# CAN_toolboard_redesign.net
KiCad netlist of a schematic drawn in EAGLE
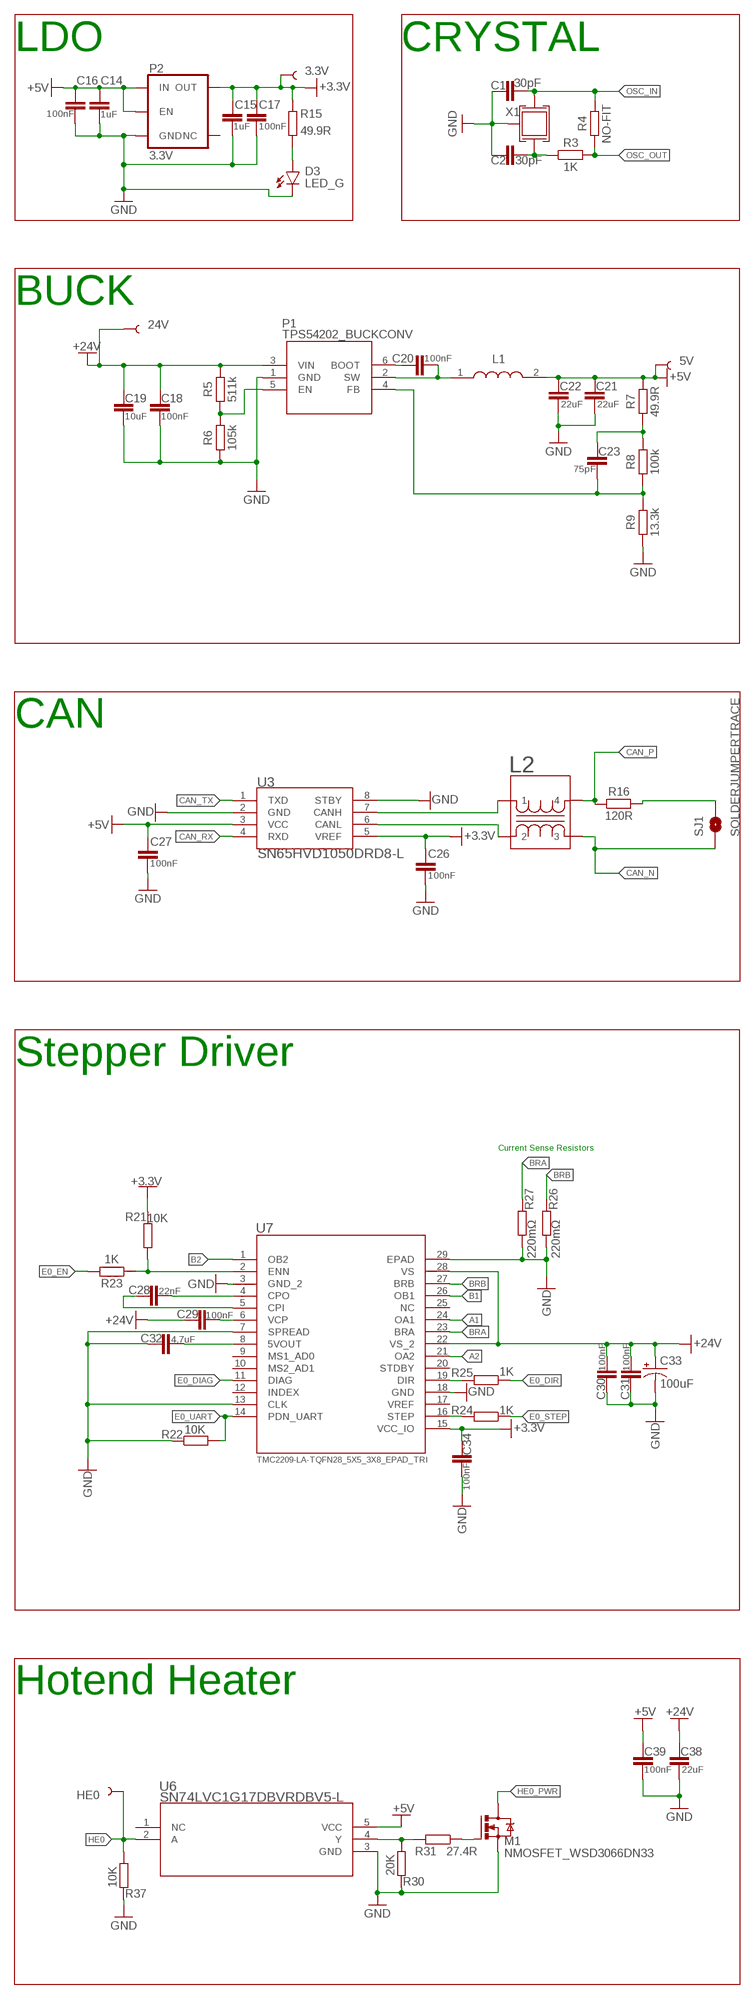
[diagram p0: schematic, sheet 1, part 1 of 2]
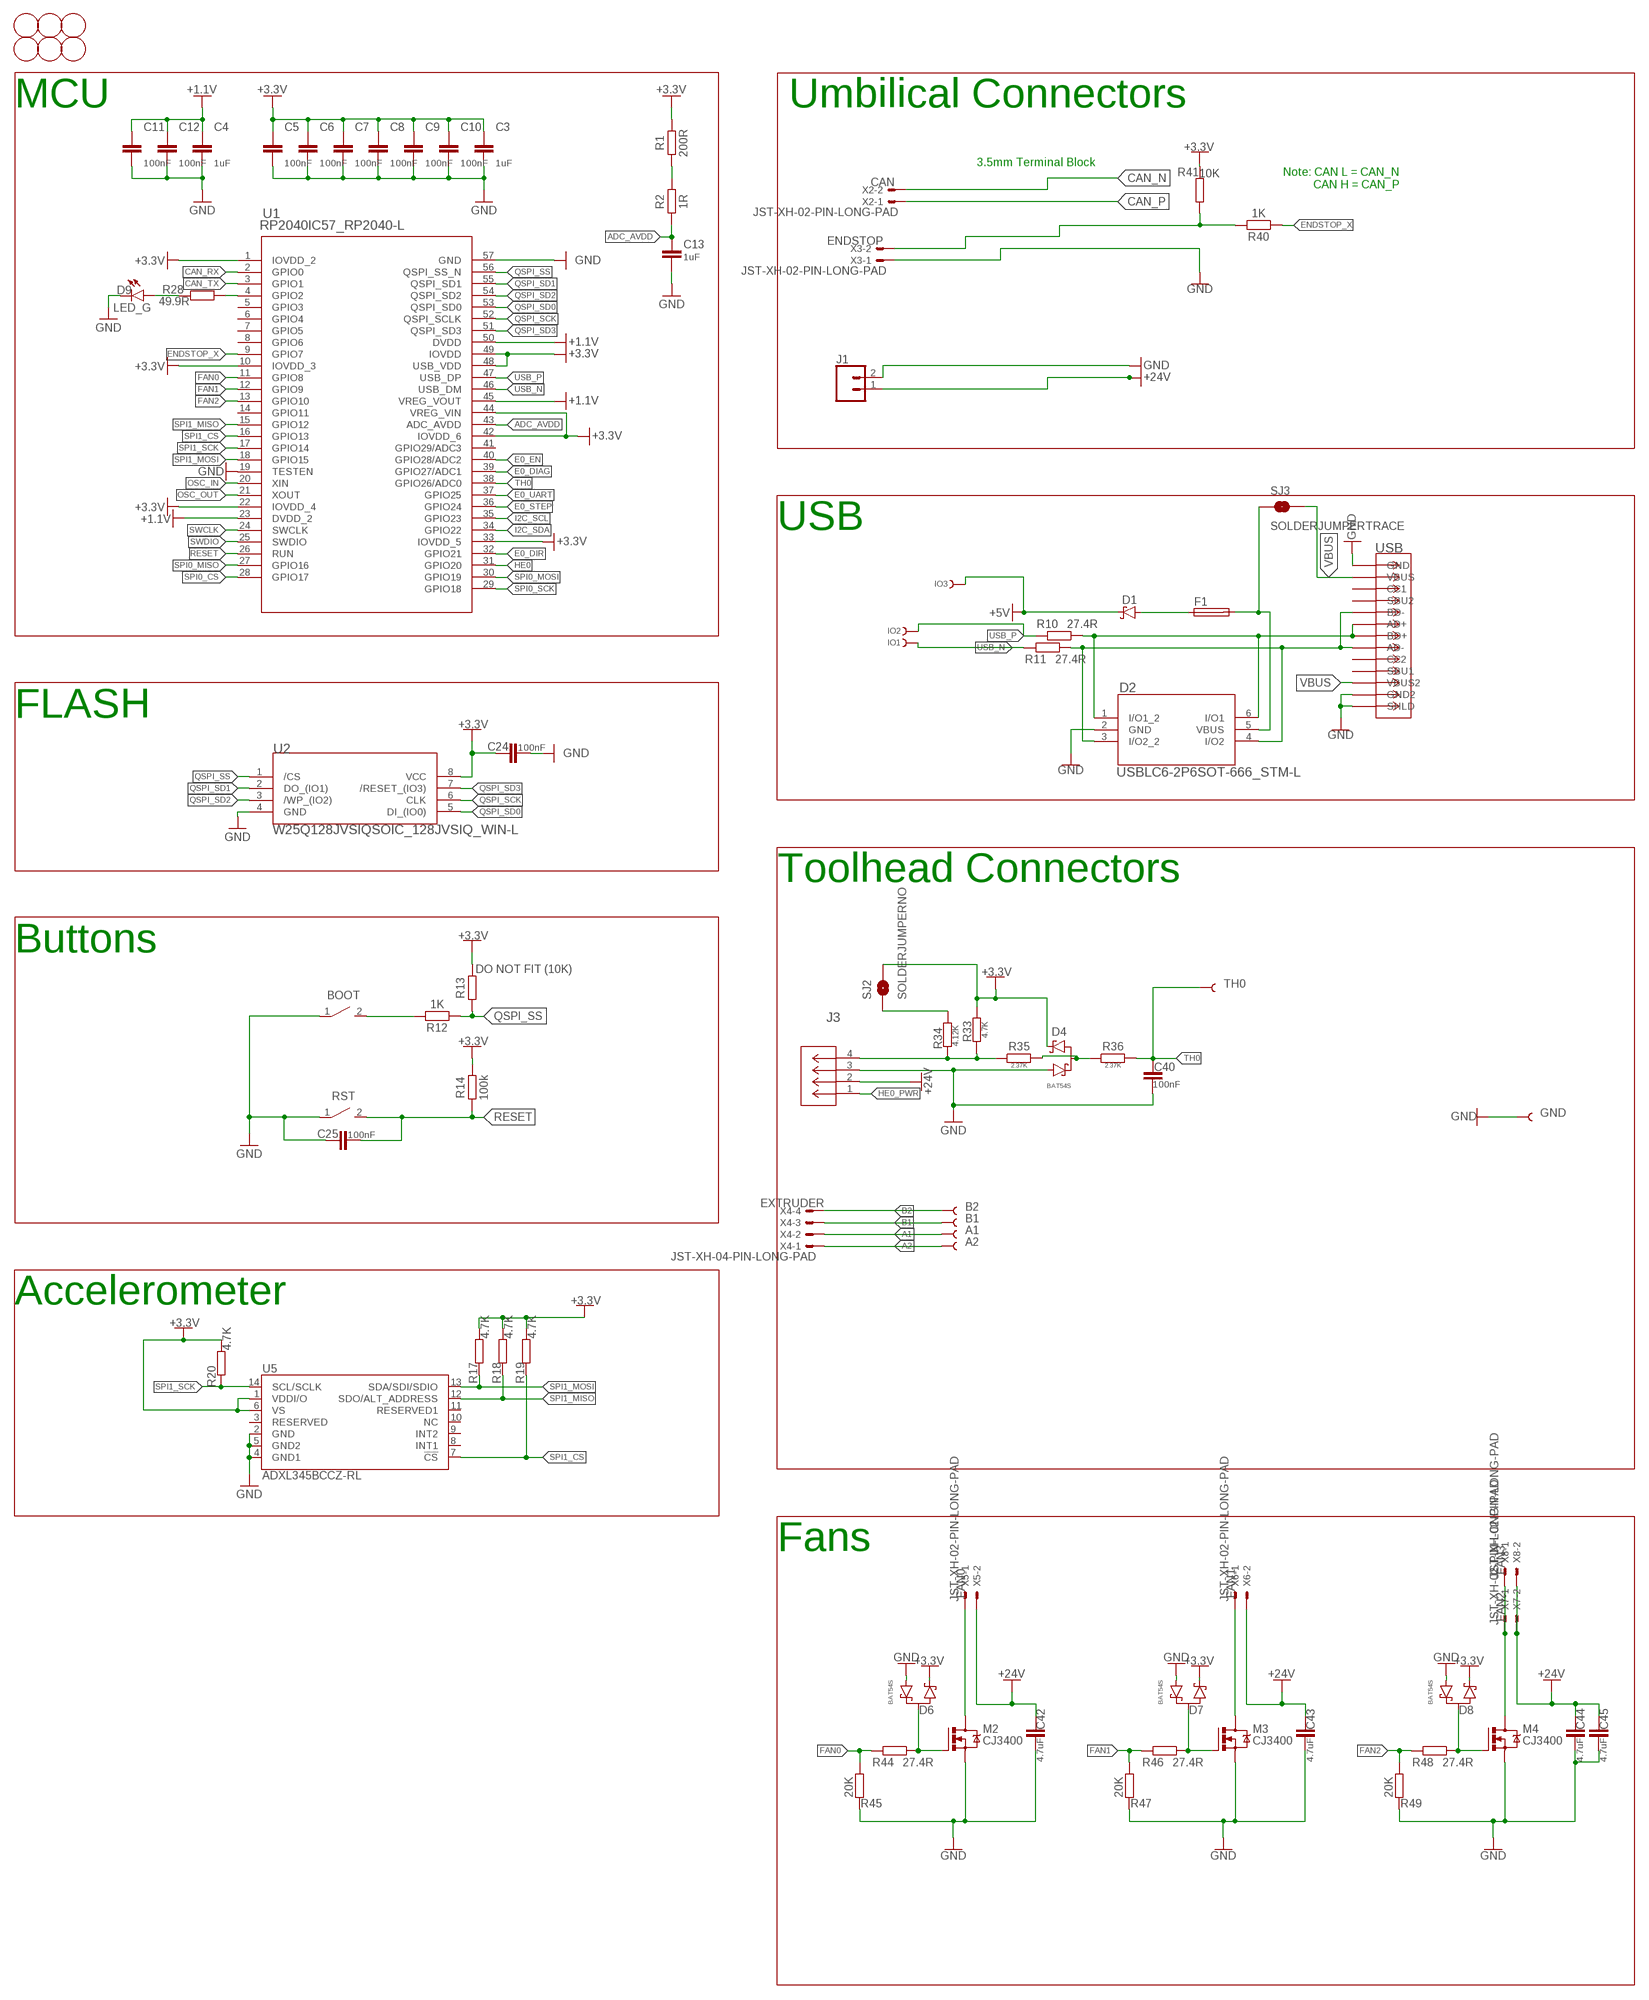
[diagram p1: schematic, sheet 1, part 2 of 2]

(export (version "E")
  (design (tool "Eeschema 10.0.6"))
  (components
    (comp (ref "3.3V")
      (value "TEST-POINT3X4")
      (footprint "eagle-import:PAD.03X.04")
      (libsource (lib "eagle-import") (part "TEST-POINT3X4"))
    )
    (comp (ref "5V")
      (value "TEST-POINT3X4")
      (footprint "eagle-import:PAD.03X.04")
      (libsource (lib "eagle-import") (part "TEST-POINT3X4"))
    )
    (comp (ref "24V")
      (value "TEST-POINT3X4")
      (footprint "eagle-import:PAD.03X.04")
      (libsource (lib "eagle-import") (part "TEST-POINT3X4"))
    )
    (comp (ref "A1")
      (value "TEST-POINT3X4")
      (footprint "eagle-import:PAD.03X.04")
      (libsource (lib "eagle-import") (part "TEST-POINT3X4"))
    )
    (comp (ref "A2")
      (value "TEST-POINT3X4")
      (footprint "eagle-import:PAD.03X.04")
      (libsource (lib "eagle-import") (part "TEST-POINT3X4"))
    )
    (comp (ref "B1")
      (value "TEST-POINT3X4")
      (footprint "eagle-import:PAD.03X.04")
      (libsource (lib "eagle-import") (part "TEST-POINT3X4"))
    )
    (comp (ref "B2")
      (value "TEST-POINT3X4")
      (footprint "eagle-import:PAD.03X.04")
      (libsource (lib "eagle-import") (part "TEST-POINT3X4"))
    )
    (comp (ref "BOOT")
      (value "B3U-1000P(M)-B")
      (footprint "eagle-import:B3U-1000P(M)-B")
      (fields (field (name "MANUFACTURER") "OMRON"))
      (libsource (lib "eagle-import") (part "B3U-X0001000P(M)-BB3U-1000P(M)-B"))
    )
    (comp (ref "C1")
      (value "30pF")
      (footprint "eagle-import:CAPC1005X60")
      (libsource (lib "eagle-import") (part "CCHIP-0402(1005-METRIC)_"))
    )
    (comp (ref "C2")
      (value "30pF")
      (footprint "eagle-import:CAPC1005X60")
      (libsource (lib "eagle-import") (part "CCHIP-0402(1005-METRIC)_"))
    )
    (comp (ref "C3")
      (value "1uF")
      (footprint "eagle-import:CAPC1005X60")
      (libsource (lib "eagle-import") (part "CCHIP-0402(1005-METRIC)_"))
    )
    (comp (ref "C4")
      (value "1uF")
      (footprint "eagle-import:CAPC1005X60")
      (libsource (lib "eagle-import") (part "CCHIP-0402(1005-METRIC)_"))
    )
    (comp (ref "C5")
      (value "100nF")
      (footprint "eagle-import:CAPC1005X60")
      (libsource (lib "eagle-import") (part "CCHIP-0402(1005-METRIC)_"))
    )
    (comp (ref "C6")
      (value "100nF")
      (footprint "eagle-import:CAPC1005X60")
      (libsource (lib "eagle-import") (part "CCHIP-0402(1005-METRIC)_"))
    )
    (comp (ref "C7")
      (value "100nF")
      (footprint "eagle-import:CAPC1005X60")
      (libsource (lib "eagle-import") (part "CCHIP-0402(1005-METRIC)_"))
    )
    (comp (ref "C8")
      (value "100nF")
      (footprint "eagle-import:CAPC1005X60")
      (libsource (lib "eagle-import") (part "CCHIP-0402(1005-METRIC)_"))
    )
    (comp (ref "C9")
      (value "100nF")
      (footprint "eagle-import:CAPC1005X60")
      (libsource (lib "eagle-import") (part "CCHIP-0402(1005-METRIC)_"))
    )
    (comp (ref "C10")
      (value "100nF")
      (footprint "eagle-import:CAPC1005X60")
      (libsource (lib "eagle-import") (part "CCHIP-0402(1005-METRIC)_"))
    )
    (comp (ref "C11")
      (value "100nF")
      (footprint "eagle-import:CAPC1005X60")
      (libsource (lib "eagle-import") (part "CCHIP-0402(1005-METRIC)_"))
    )
    (comp (ref "C12")
      (value "100nF")
      (footprint "eagle-import:CAPC1005X60")
      (libsource (lib "eagle-import") (part "CCHIP-0402(1005-METRIC)_"))
    )
    (comp (ref "C13")
      (value "1uF")
      (footprint "eagle-import:CAPC1005X60")
      (libsource (lib "eagle-import") (part "CCHIP-0402(1005-METRIC)_"))
    )
    (comp (ref "C14")
      (value "1uF")
      (footprint "eagle-import:CAPC1005X60")
      (libsource (lib "eagle-import") (part "CCHIP-0402(1005-METRIC)_"))
    )
    (comp (ref "C15")
      (value "1uF")
      (footprint "eagle-import:CAPC1005X60")
      (libsource (lib "eagle-import") (part "CCHIP-0402(1005-METRIC)_"))
    )
    (comp (ref "C16")
      (value "100nF")
      (footprint "eagle-import:CAPC1005X60")
      (libsource (lib "eagle-import") (part "CCHIP-0402(1005-METRIC)_"))
    )
    (comp (ref "C17")
      (value "100nF")
      (footprint "eagle-import:CAPC1005X60")
      (libsource (lib "eagle-import") (part "CCHIP-0402(1005-METRIC)_"))
    )
    (comp (ref "C18")
      (value "100nF")
      (footprint "eagle-import:CAPC1005X60")
      (libsource (lib "eagle-import") (part "CCHIP-0402(1005-METRIC)_"))
    )
    (comp (ref "C19")
      (value "10uF")
      (footprint "eagle-import:CAPC1608X85")
      (libsource (lib "eagle-import") (part "CCHIP-0603(1608-METRIC)_"))
    )
    (comp (ref "C20")
      (value "100nF")
      (footprint "eagle-import:CAPC1005X60")
      (libsource (lib "eagle-import") (part "CCHIP-0402(1005-METRIC)_"))
    )
    (comp (ref "C21")
      (value "22uF")
      (footprint "eagle-import:CAPC2012X110")
      (libsource (lib "eagle-import") (part "CCHIP-0805(2012-METRIC)_"))
    )
    (comp (ref "C22")
      (value "22uF")
      (footprint "eagle-import:CAPC2012X110")
      (libsource (lib "eagle-import") (part "CCHIP-0805(2012-METRIC)_"))
    )
    (comp (ref "C23")
      (value "75pF")
      (footprint "eagle-import:CAPC1005X60")
      (libsource (lib "eagle-import") (part "CCHIP-0402(1005-METRIC)_"))
    )
    (comp (ref "C24")
      (value "100nF")
      (footprint "eagle-import:CAPC1005X60")
      (libsource (lib "eagle-import") (part "CCHIP-0402(1005-METRIC)_"))
    )
    (comp (ref "C25")
      (value "100nF")
      (footprint "eagle-import:CAPC1005X60")
      (libsource (lib "eagle-import") (part "CCHIP-0402(1005-METRIC)_"))
    )
    (comp (ref "C26")
      (value "100nF")
      (footprint "eagle-import:CAPC1005X60")
      (libsource (lib "eagle-import") (part "CCHIP-0402(1005-METRIC)_"))
    )
    (comp (ref "C27")
      (value "100nF")
      (footprint "eagle-import:CAPC1005X60")
      (libsource (lib "eagle-import") (part "CCHIP-0402(1005-METRIC)_"))
    )
    (comp (ref "C28")
      (value "22nF")
      (footprint "eagle-import:CAPC1005X60")
      (libsource (lib "eagle-import") (part "CCHIP-0402(1005-METRIC)_"))
    )
    (comp (ref "C29")
      (value "100nF")
      (footprint "eagle-import:CAPC1005X60")
      (libsource (lib "eagle-import") (part "CCHIP-0402(1005-METRIC)_"))
    )
    (comp (ref "C30")
      (value "100nF")
      (footprint "eagle-import:CAPC1005X60")
      (libsource (lib "eagle-import") (part "CCHIP-0402(1005-METRIC)_"))
    )
    (comp (ref "C31")
      (value "100nF")
      (footprint "eagle-import:CAPC1005X60")
      (libsource (lib "eagle-import") (part "CCHIP-0402(1005-METRIC)_"))
    )
    (comp (ref "C32")
      (value "4.7uF")
      (footprint "eagle-import:CAPC1608X85")
      (libsource (lib "eagle-import") (part "CCHIP-0603(1608-METRIC)_"))
    )
    (comp (ref "C33")
      (value "100uF")
      (footprint "eagle-import:PANASONIC_D")
      (libsource (lib "eagle-import") (part "100UF-POLAR-25V-20%(ELEC)"))
    )
    (comp (ref "C34")
      (value "100nF")
      (footprint "eagle-import:CAPC1005X60")
      (libsource (lib "eagle-import") (part "CCHIP-0402(1005-METRIC)_"))
    )
    (comp (ref "C38")
      (value "22uF")
      (footprint "eagle-import:CAPC2012X110")
      (libsource (lib "eagle-import") (part "CCHIP-0805(2012-METRIC)_"))
    )
    (comp (ref "C39")
      (value "100nF")
      (footprint "eagle-import:CAPC1005X60")
      (libsource (lib "eagle-import") (part "CCHIP-0402(1005-METRIC)_"))
    )
    (comp (ref "C40")
      (value "100nF")
      (footprint "eagle-import:CAPC1005X60")
      (libsource (lib "eagle-import") (part "CCHIP-0402(1005-METRIC)_"))
    )
    (comp (ref "C42")
      (value "4.7uF")
      (footprint "eagle-import:CAPC1608X85")
      (libsource (lib "eagle-import") (part "CCHIP-0603(1608-METRIC)_"))
    )
    (comp (ref "C43")
      (value "4.7uF")
      (footprint "eagle-import:CAPC1608X85")
      (libsource (lib "eagle-import") (part "CCHIP-0603(1608-METRIC)_"))
    )
    (comp (ref "C44")
      (value "4.7uF")
      (footprint "eagle-import:CAPC1608X85")
      (libsource (lib "eagle-import") (part "CCHIP-0603(1608-METRIC)_"))
    )
    (comp (ref "C45")
      (value "4.7uF")
      (footprint "eagle-import:CAPC1608X85")
      (libsource (lib "eagle-import") (part "CCHIP-0603(1608-METRIC)_"))
    )
    (comp (ref "D1")
      (value "MBR0520LT1G")
      (footprint "eagle-import:SODFL3718X115")
      (fields (field (name "MANUFACTURER") "ON Semiconductor"))
      (libsource (lib "eagle-import") (part "SCHOTTKY_DO-219MBR0520LT1G"))
    )
    (comp (ref "D2")
      (value "USBLC6-2P6SOT-666_STM-L")
      (footprint "eagle-import:SOT-666_STM-L")
      (fields
        (field (name "MANUFACTURER_PART_NUMBER") "USBLC6-2P6")
        (field (name "COPYRIGHT") "Copyright (C) 2023 Ultra Librarian. All rights reserved.")
      )
      (libsource (lib "eagle-import") (part "USBLC6-2P6SOT-666_STM-L"))
    )
    (comp (ref "D3")
      (value "LED_G")
      (footprint "eagle-import:LEDC1608X35N_FLAT-G")
      (libsource (lib "eagle-import") (part "CHIP-FLAT-G_0603-0.35MM"))
    )
    (comp (ref "D4")
      (value "BAT54S")
      (footprint "eagle-import:SOT23")
      (libsource (lib "eagle-import") (part "BAT54S"))
    )
    (comp (ref "D6")
      (value "BAT54S")
      (footprint "eagle-import:SOT23")
      (libsource (lib "eagle-import") (part "BAT54S"))
    )
    (comp (ref "D7")
      (value "BAT54S")
      (footprint "eagle-import:SOT23")
      (libsource (lib "eagle-import") (part "BAT54S"))
    )
    (comp (ref "D8")
      (value "BAT54S")
      (footprint "eagle-import:SOT23")
      (libsource (lib "eagle-import") (part "BAT54S"))
    )
    (comp (ref "D9")
      (value "LED_G")
      (footprint "eagle-import:LEDC1608X35N_FLAT-G")
      (libsource (lib "eagle-import") (part "CHIP-FLAT-G_0603-0.35MM"))
    )
    (comp (ref "F1")
      (value "FUSE_CHIP-0603(1608-METRIC)")
      (footprint "eagle-import:FUSC1608X60N")
      (libsource (lib "eagle-import") (part "FUSECHIP-0603(1608-METRIC)_"))
    )
    (comp (ref "FD1")
      (value "FIDUCIAL")
      (footprint "eagle-import:FIDUCIAL_1MM")
      (libsource (lib "eagle-import") (part "FIDUCIAL"))
    )
    (comp (ref "FD2")
      (value "FIDUCIAL")
      (footprint "eagle-import:FIDUCIAL_1MM")
      (libsource (lib "eagle-import") (part "FIDUCIAL"))
    )
    (comp (ref "FD3")
      (value "FIDUCIAL")
      (footprint "eagle-import:FIDUCIAL_1MM")
      (libsource (lib "eagle-import") (part "FIDUCIAL"))
    )
    (comp (ref "FD4")
      (value "FIDUCIAL")
      (footprint "eagle-import:FIDUCIAL_1MM")
      (libsource (lib "eagle-import") (part "FIDUCIAL"))
    )
    (comp (ref "FD5")
      (value "FIDUCIAL")
      (footprint "eagle-import:FIDUCIAL_1MM")
      (libsource (lib "eagle-import") (part "FIDUCIAL"))
    )
    (comp (ref "FD6")
      (value "FIDUCIAL")
      (footprint "eagle-import:FIDUCIAL_1MM")
      (libsource (lib "eagle-import") (part "FIDUCIAL"))
    )
    (comp (ref "GND")
      (value "TEST-POINT3X4")
      (footprint "eagle-import:PAD.03X.04")
      (libsource (lib "eagle-import") (part "TEST-POINT3X4"))
    )
    (comp (ref "HE0")
      (value "TEST-POINT3X4")
      (footprint "eagle-import:PAD.03X.04")
      (libsource (lib "eagle-import") (part "TEST-POINT3X4"))
    )
    (comp (ref "IO1")
      (value "TEST-POINT3")
      (footprint "eagle-import:PAD.03X.03")
      (libsource (lib "eagle-import") (part "TEST-POINT3"))
    )
    (comp (ref "IO2")
      (value "TEST-POINT3")
      (footprint "eagle-import:PAD.03X.03")
      (libsource (lib "eagle-import") (part "TEST-POINT3"))
    )
    (comp (ref "IO3")
      (value "TEST-POINT3")
      (footprint "eagle-import:PAD.03X.03")
      (libsource (lib "eagle-import") (part "TEST-POINT3"))
    )
    (comp (ref "J1")
      (value "CONN_023.5MM")
      (footprint "eagle-import:SCREWTERMINAL-3.5MM-2")
      (libsource (lib "eagle-import") (part "CONN_023.5MM"))
    )
    (comp (ref "J3")
      (value "430450400CON_430450400_MOL")
      (footprint "eagle-import:CON_430450400_MOL")
      (fields
        (field (name "MANUFACTURER_PART_NUMBER") "430450400")
        (field (name "COPYRIGHT") "Copyright (C) 2023 Ultra Librarian. All rights reserved.")
      )
      (libsource (lib "eagle-import") (part "430450400CON_430450400_MOL"))
    )
    (comp (ref "L1")
      (value "ASPI-0630HI-100M-T157X7X4")
      (footprint "eagle-import:SMDRI74-680MT")
      (libsource (lib "eagle-import") (part "ASPI-0630HI-100M-T157X7X4"))
    )
    (comp (ref "L2")
      (value "ACM2012-201-2P-T002ACM2012_TDK")
      (footprint "eagle-import:ACM2012_TDK")
      (fields
        (field (name "MANUFACTURER_PART_NUMBER") "ACM2012-201-2P-T002")
        (field (name "COPYRIGHT") "Copyright (C) 2023 Ultra Librarian. All rights reserved.")
      )
      (libsource (lib "eagle-import") (part "ACM2012-201-2P-T002ACM2012_TDK"))
    )
    (comp (ref "M1")
      (value "NMOSFET_WSD3066DN33")
      (footprint "eagle-import:NMOSFET_WSD3066DN33")
      (libsource (lib "eagle-import") (part "NMOSFET_WSD3066DN33"))
    )
    (comp (ref "M2")
      (value "CJ3400")
      (footprint "eagle-import:SOT23")
      (fields (field (name "MANUFACTURER") "ON Semiconductor") (field (name "MPN") "BSS123L"))
      (libsource (lib "eagle-import") (part "NMOSFET__SOT23-GSDBSS123"))
    )
    (comp (ref "M3")
      (value "CJ3400")
      (footprint "eagle-import:SOT23")
      (fields (field (name "MANUFACTURER") "ON Semiconductor") (field (name "MPN") "BSS123L"))
      (libsource (lib "eagle-import") (part "NMOSFET__SOT23-GSDBSS123"))
    )
    (comp (ref "M4")
      (value "CJ3400")
      (footprint "eagle-import:SOT23")
      (fields (field (name "MANUFACTURER") "ON Semiconductor") (field (name "MPN") "BSS123L"))
      (libsource (lib "eagle-import") (part "NMOSFET__SOT23-GSDBSS123"))
    )
    (comp (ref "P1")
      (value "TPS54202_BUCKCONV")
      (footprint "eagle-import:SOT-23-6")
      (libsource (lib "eagle-import") (part "TPS54202_BUCKCONV"))
    )
    (comp (ref "P2")
      (value "3.3V")
      (footprint "eagle-import:SOT23-5")
      (libsource (lib "eagle-import") (part "V_REG_AP2112K-3.3V"))
    )
    (comp (ref "R1")
      (value "200R")
      (footprint "eagle-import:RESC1005X40")
      (libsource (lib "eagle-import") (part "RCHIP-0402(1005-METRIC)_"))
    )
    (comp (ref "R2")
      (value "1R")
      (footprint "eagle-import:RESC1005X40")
      (libsource (lib "eagle-import") (part "RCHIP-0402(1005-METRIC)_"))
    )
    (comp (ref "R3")
      (value "1K")
      (footprint "eagle-import:RESC1005X40")
      (libsource (lib "eagle-import") (part "RCHIP-0402(1005-METRIC)_"))
    )
    (comp (ref "R4")
      (value "NO-FIT")
      (footprint "eagle-import:RESC1005X40")
      (libsource (lib "eagle-import") (part "RCHIP-0402(1005-METRIC)_"))
    )
    (comp (ref "R5")
      (value "511k")
      (footprint "eagle-import:RESC1005X40")
      (libsource (lib "eagle-import") (part "RCHIP-0402(1005-METRIC)_"))
    )
    (comp (ref "R6")
      (value "105k")
      (footprint "eagle-import:RESC1005X40")
      (libsource (lib "eagle-import") (part "RCHIP-0402(1005-METRIC)_"))
    )
    (comp (ref "R7")
      (value "49.9R")
      (footprint "eagle-import:RESC1005X40")
      (libsource (lib "eagle-import") (part "RCHIP-0402(1005-METRIC)_"))
    )
    (comp (ref "R8")
      (value "100k")
      (footprint "eagle-import:RESC1005X40")
      (libsource (lib "eagle-import") (part "RCHIP-0402(1005-METRIC)_"))
    )
    (comp (ref "R9")
      (value "13.3k")
      (footprint "eagle-import:RESC1005X40")
      (libsource (lib "eagle-import") (part "RCHIP-0402(1005-METRIC)_"))
    )
    (comp (ref "R10")
      (value "27.4R")
      (footprint "eagle-import:RESC1005X40")
      (libsource (lib "eagle-import") (part "RCHIP-0402(1005-METRIC)_"))
    )
    (comp (ref "R11")
      (value "27.4R")
      (footprint "eagle-import:RESC1005X40")
      (libsource (lib "eagle-import") (part "RCHIP-0402(1005-METRIC)_"))
    )
    (comp (ref "R12")
      (value "1K")
      (footprint "eagle-import:RESC1005X40")
      (libsource (lib "eagle-import") (part "RCHIP-0402(1005-METRIC)_"))
    )
    (comp (ref "R13")
      (value "DO NOT FIT (10K)")
      (footprint "eagle-import:RESC1005X40")
      (libsource (lib "eagle-import") (part "RCHIP-0402(1005-METRIC)_"))
    )
    (comp (ref "R14")
      (value "100k")
      (footprint "eagle-import:RESC1005X40")
      (libsource (lib "eagle-import") (part "RCHIP-0402(1005-METRIC)_"))
    )
    (comp (ref "R15")
      (value "49.9R")
      (footprint "eagle-import:RESC1005X40")
      (libsource (lib "eagle-import") (part "RCHIP-0402(1005-METRIC)_"))
    )
    (comp (ref "R16")
      (value "120R")
      (footprint "eagle-import:RESC1005X40")
      (libsource (lib "eagle-import") (part "RCHIP-0402(1005-METRIC)_"))
    )
    (comp (ref "R17")
      (value "4.7K")
      (footprint "eagle-import:RESC1005X40")
      (libsource (lib "eagle-import") (part "RCHIP-0402(1005-METRIC)_"))
    )
    (comp (ref "R18")
      (value "4.7K")
      (footprint "eagle-import:RESC1005X40")
      (libsource (lib "eagle-import") (part "RCHIP-0402(1005-METRIC)_"))
    )
    (comp (ref "R19")
      (value "4.7K")
      (footprint "eagle-import:RESC1005X40")
      (libsource (lib "eagle-import") (part "RCHIP-0402(1005-METRIC)_"))
    )
    (comp (ref "R20")
      (value "4.7K")
      (footprint "eagle-import:RESC1005X40")
      (libsource (lib "eagle-import") (part "RCHIP-0402(1005-METRIC)_"))
    )
    (comp (ref "R21")
      (value "10K")
      (footprint "eagle-import:RESC1005X40")
      (libsource (lib "eagle-import") (part "RCHIP-0402(1005-METRIC)_"))
    )
    (comp (ref "R22")
      (value "10K")
      (footprint "eagle-import:RESC1005X40")
      (libsource (lib "eagle-import") (part "RCHIP-0402(1005-METRIC)_"))
    )
    (comp (ref "R23")
      (value "1K")
      (footprint "eagle-import:RESC1005X40")
      (libsource (lib "eagle-import") (part "RCHIP-0402(1005-METRIC)_"))
    )
    (comp (ref "R24")
      (value "1K")
      (footprint "eagle-import:RESC1005X40")
      (libsource (lib "eagle-import") (part "RCHIP-0402(1005-METRIC)_"))
    )
    (comp (ref "R25")
      (value "1K")
      (footprint "eagle-import:RESC1005X40")
      (libsource (lib "eagle-import") (part "RCHIP-0402(1005-METRIC)_"))
    )
    (comp (ref "R26")
      (value "220mΩ")
      (footprint "eagle-import:RESC1005X40")
      (libsource (lib "eagle-import") (part "RCHIP-0402(1005-METRIC)_"))
    )
    (comp (ref "R27")
      (value "220mΩ")
      (footprint "eagle-import:RESC1005X40")
      (libsource (lib "eagle-import") (part "RCHIP-0402(1005-METRIC)_"))
    )
    (comp (ref "R28")
      (value "49.9R")
      (footprint "eagle-import:RESC1005X40")
      (libsource (lib "eagle-import") (part "RCHIP-0402(1005-METRIC)_"))
    )
    (comp (ref "R30")
      (value "20K")
      (footprint "eagle-import:RESC1005X40")
      (libsource (lib "eagle-import") (part "RCHIP-0402(1005-METRIC)_"))
    )
    (comp (ref "R31")
      (value "27.4R")
      (footprint "eagle-import:RESC1005X40")
      (libsource (lib "eagle-import") (part "RCHIP-0402(1005-METRIC)_"))
    )
    (comp (ref "R33")
      (value "4.7K")
      (footprint "eagle-import:RESC1005X40")
      (libsource (lib "eagle-import") (part "RCHIP-0402(1005-METRIC)_"))
    )
    (comp (ref "R34")
      (value "4.12K")
      (footprint "eagle-import:RESC1005X40")
      (libsource (lib "eagle-import") (part "RCHIP-0402(1005-METRIC)_"))
    )
    (comp (ref "R35")
      (value "2.37K")
      (footprint "eagle-import:RESC1005X40")
      (libsource (lib "eagle-import") (part "RCHIP-0402(1005-METRIC)_"))
    )
    (comp (ref "R36")
      (value "2.37K")
      (footprint "eagle-import:RESC1005X40")
      (libsource (lib "eagle-import") (part "RCHIP-0402(1005-METRIC)_"))
    )
    (comp (ref "R37")
      (value "10K")
      (footprint "eagle-import:RESC1005X40")
      (libsource (lib "eagle-import") (part "RCHIP-0402(1005-METRIC)_"))
    )
    (comp (ref "R40")
      (value "1K")
      (footprint "eagle-import:RESC1005X40")
      (libsource (lib "eagle-import") (part "RCHIP-0402(1005-METRIC)_"))
    )
    (comp (ref "R41")
      (value "10K")
      (footprint "eagle-import:RESC1005X40")
      (libsource (lib "eagle-import") (part "RCHIP-0402(1005-METRIC)_"))
    )
    (comp (ref "R44")
      (value "27.4R")
      (footprint "eagle-import:RESC1005X40")
      (libsource (lib "eagle-import") (part "RCHIP-0402(1005-METRIC)_"))
    )
    (comp (ref "R45")
      (value "20K")
      (footprint "eagle-import:RESC1005X40")
      (libsource (lib "eagle-import") (part "RCHIP-0402(1005-METRIC)_"))
    )
    (comp (ref "R46")
      (value "27.4R")
      (footprint "eagle-import:RESC1005X40")
      (libsource (lib "eagle-import") (part "RCHIP-0402(1005-METRIC)_"))
    )
    (comp (ref "R47")
      (value "20K")
      (footprint "eagle-import:RESC1005X40")
      (libsource (lib "eagle-import") (part "RCHIP-0402(1005-METRIC)_"))
    )
    (comp (ref "R48")
      (value "27.4R")
      (footprint "eagle-import:RESC1005X40")
      (libsource (lib "eagle-import") (part "RCHIP-0402(1005-METRIC)_"))
    )
    (comp (ref "R49")
      (value "20K")
      (footprint "eagle-import:RESC1005X40")
      (libsource (lib "eagle-import") (part "RCHIP-0402(1005-METRIC)_"))
    )
    (comp (ref "RST")
      (value "B3U-1000P(M)-B")
      (footprint "eagle-import:B3U-1000P(M)-B")
      (fields (field (name "MANUFACTURER") "OMRON"))
      (libsource (lib "eagle-import") (part "B3U-X0001000P(M)-BB3U-1000P(M)-B"))
    )
    (comp (ref "SJ1")
      (value "SOLDERJUMPERTRACE")
      (footprint "eagle-import:SJ_2S-TRACE")
      (libsource (lib "eagle-import") (part "SOLDERJUMPERTRACE"))
    )
    (comp (ref "SJ2")
      (value "SOLDERJUMPERNO")
      (footprint "eagle-import:SJ_2S-NO")
      (libsource (lib "eagle-import") (part "SOLDERJUMPERNO"))
    )
    (comp (ref "SJ3")
      (value "SOLDERJUMPERTRACE")
      (footprint "eagle-import:SJ_2S-TRACE")
      (libsource (lib "eagle-import") (part "SOLDERJUMPERTRACE"))
    )
    (comp (ref "TH0")
      (value "TEST-POINT3X4")
      (footprint "eagle-import:PAD.03X.04")
      (libsource (lib "eagle-import") (part "TEST-POINT3X4"))
    )
    (comp (ref "U1")
      (value "RP2040IC57_RP2040-L")
      (footprint "eagle-import:IC57_RP2040-L")
      (fields
        (field (name "MANUFACTURER_PART_NUMBER") "RP2040")
        (field (name "COPYRIGHT") "Copyright (C) 2023 Ultra Librarian. All rights reserved.")
      )
      (libsource (lib "eagle-import") (part "RP2040IC57_RP2040-L"))
    )
    (comp (ref "U2")
      (value "W25Q128JVSIQSOIC_128JVSIQ_WIN-L")
      (footprint "eagle-import:SOIC_128JVSIQ_WIN-L")
      (fields
        (field (name "MANUFACTURER_PART_NUMBER") "W25Q128JVSIQ")
        (field (name "COPYRIGHT") "Copyright (C) 2023 Ultra Librarian. All rights reserved.")
      )
      (libsource (lib "eagle-import") (part "W25Q128JVSIQSOIC_128JVSIQ_WIN-L"))
    )
    (comp (ref "U3")
      (value "SN65HVD1050DRD8-L")
      (footprint "eagle-import:D8-L")
      (fields
        (field (name "MANUFACTURER_PART_NUMBER") "SN65HVD1050DR")
        (field (name "COPYRIGHT") "Copyright (C) 2023 Ultra Librarian. All rights reserved.")
      )
      (libsource (lib "eagle-import") (part "SN65HVD1050DRD8-L"))
    )
    (comp (ref "U5")
      (value "ADXL345BCCZ-RL")
      (footprint "eagle-import:ADXL345_LGA14")
      (fields (field (name "MANUFACTURER") "ANALOG DEVICES"))
      (libsource (lib "eagle-import") (part "ADXL345BCCZ-RL"))
    )
    (comp (ref "U6")
      (value "SN74LVC1G17DBVRDBV5-L")
      (footprint "eagle-import:DBV5-L")
      (fields
        (field (name "MANUFACTURER_PART_NUMBER") "SN74LVC1G17DBVR")
        (field (name "COPYRIGHT") "Copyright (C) 2023 Ultra Librarian. All rights reserved.")
      )
      (libsource (lib "eagle-import") (part "SN74LVC1G17DBVRDBV5-L"))
    )
    (comp (ref "U7")
      (value "TMC2209-LA-TQFN28_5X5_3X8_EPAD_TRI")
      (footprint "eagle-import:QFN28_5X5_3X8_EPAD_TRI")
      (fields
        (field (name "MANUFACTURER_PART_NUMBER") "TMC2209-LA-T")
        (field (name "COPYRIGHT") "Copyright (C) 2023 Ultra Librarian. All rights reserved.")
      )
      (libsource (lib "eagle-import") (part "TMC2209-LA-TQFN28_5X5_3X8_EPAD_TRI"))
    )
    (comp (ref "USB")
      (value "USB-C(DX07S016JA1R1500)")
      (footprint "eagle-import:CONN12_016JA1R1500_JAE")
      (fields
        (field (name "MANUFACTURER_PART_NUMBER") "DX07S016JA1R1500")
        (field (name "COPYRIGHT") "Copyright (C) 2018 Accelerated Designs. All rights reserved")
      )
      (libsource (lib "eagle-import") (part "USB-C(DX07S016JA1R1500)"))
    )
    (comp (ref "X1")
      (value "CRYSTAL_TAXM12M4RLBDDT2T_3225")
      (footprint "eagle-import:CRYSTAL_3225")
      (libsource (lib "eagle-import") (part "CRYSTAL_TAXM12M4RLBDDT2T_3225"))
    )
    (comp (ref "X2")
      (value "JST-XH-02-PIN-LONG-PAD")
      (footprint "eagle-import:JST-XH-02-PACKAGE-LONG-PAD")
      (libsource (lib "eagle-import") (part "JST-XH-02-PIN-LONG-PAD"))
    )
    (comp (ref "X3")
      (value "JST-XH-02-PIN-LONG-PAD")
      (footprint "eagle-import:JST-XH-02-PACKAGE-LONG-PAD")
      (libsource (lib "eagle-import") (part "JST-XH-02-PIN-LONG-PAD"))
    )
    (comp (ref "X4")
      (value "JST-XH-04-PIN-LONG-PAD")
      (footprint "eagle-import:JST-XH-04-PACKAGE-LONG-PAD")
      (libsource (lib "eagle-import") (part "JST-XH-04-PIN-LONG-PAD"))
    )
    (comp (ref "X5")
      (value "JST-XH-02-PIN-LONG-PAD")
      (footprint "eagle-import:JST-XH-02-PACKAGE-LONG-PAD")
      (libsource (lib "eagle-import") (part "JST-XH-02-PIN-LONG-PAD"))
    )
    (comp (ref "X6")
      (value "JST-XH-02-PIN-LONG-PAD")
      (footprint "eagle-import:JST-XH-02-PACKAGE-LONG-PAD")
      (libsource (lib "eagle-import") (part "JST-XH-02-PIN-LONG-PAD"))
    )
    (comp (ref "X7")
      (value "JST-XH-02-PIN-LONG-PAD")
      (footprint "eagle-import:JST-XH-02-PACKAGE-LONG-PAD")
      (libsource (lib "eagle-import") (part "JST-XH-02-PIN-LONG-PAD"))
    )
    (comp (ref "X8")
      (value "JST-XH-02-PIN-LONG-PAD")
      (footprint "eagle-import:JST-XH-02-PACKAGE-LONG-PAD")
      (libsource (lib "eagle-import") (part "JST-XH-02-PIN-LONG-PAD"))
    )
  )
  (nets
    (net (code "1") (name "+1.1V") (class "Default")
      (node (ref "C11") (pin "1") (pinfunction "1_1") (pintype "passive"))
      (node (ref "C12") (pin "1") (pinfunction "1_1") (pintype "passive"))
      (node (ref "C4") (pin "1") (pinfunction "1_1") (pintype "passive"))
      (node (ref "U1") (pin "23") (pinfunction "DVDD_2_23") (pintype "power_in"))
      (node (ref "U1") (pin "45") (pinfunction "VREG_VOUT_45") (pintype "output"))
      (node (ref "U1") (pin "50") (pinfunction "DVDD_50") (pintype "power_in"))
    )
    (net (code "2") (name "+3.3V") (class "Default")
      (node (ref "3.3V") (pin "P$1") (pinfunction "1_P$1") (pintype "bidirectional"))
      (node (ref "C10") (pin "1") (pinfunction "1_1") (pintype "passive"))
      (node (ref "C15") (pin "1") (pinfunction "1_1") (pintype "passive"))
      (node (ref "C17") (pin "1") (pinfunction "1_1") (pintype "passive"))
      (node (ref "C24") (pin "1") (pinfunction "1_1") (pintype "passive"))
      (node (ref "C26") (pin "1") (pinfunction "1_1") (pintype "passive"))
      (node (ref "C3") (pin "1") (pinfunction "1_1") (pintype "passive"))
      (node (ref "C34") (pin "1") (pinfunction "1_1") (pintype "passive"))
      (node (ref "C5") (pin "1") (pinfunction "1_1") (pintype "passive"))
      (node (ref "C6") (pin "1") (pinfunction "1_1") (pintype "passive"))
      (node (ref "C7") (pin "1") (pinfunction "1_1") (pintype "passive"))
      (node (ref "C8") (pin "1") (pinfunction "1_1") (pintype "passive"))
      (node (ref "C9") (pin "1") (pinfunction "1_1") (pintype "passive"))
      (node (ref "D4") (pin "2") (pinfunction "2_2") (pintype "passive"))
      (node (ref "D6") (pin "2") (pinfunction "2_2") (pintype "passive"))
      (node (ref "D7") (pin "2") (pinfunction "2_2") (pintype "passive"))
      (node (ref "D8") (pin "2") (pinfunction "2_2") (pintype "passive"))
      (node (ref "P2") (pin "5") (pinfunction "OUT_5") (pintype "passive"))
      (node (ref "R1") (pin "2") (pinfunction "2_2") (pintype "passive"))
      (node (ref "R13") (pin "2") (pinfunction "2_2") (pintype "passive"))
      (node (ref "R14") (pin "2") (pinfunction "2_2") (pintype "passive"))
      (node (ref "R15") (pin "2") (pinfunction "2_2") (pintype "passive"))
      (node (ref "R17") (pin "2") (pinfunction "2_2") (pintype "passive"))
      (node (ref "R18") (pin "2") (pinfunction "2_2") (pintype "passive"))
      (node (ref "R19") (pin "2") (pinfunction "2_2") (pintype "passive"))
      (node (ref "R20") (pin "2") (pinfunction "2_2") (pintype "passive"))
      (node (ref "R21") (pin "1") (pinfunction "1_1") (pintype "passive"))
      (node (ref "R33") (pin "2") (pinfunction "2_2") (pintype "passive"))
      (node (ref "R41") (pin "1") (pinfunction "1_1") (pintype "passive"))
      (node (ref "SJ2") (pin "2") (pinfunction "2_2") (pintype "passive"))
      (node (ref "U1") (pin "1") (pinfunction "IOVDD_2_1") (pintype "power_in"))
      (node (ref "U1") (pin "10") (pinfunction "IOVDD_3_10") (pintype "power_in"))
      (node (ref "U1") (pin "22") (pinfunction "IOVDD_4_22") (pintype "power_in"))
      (node (ref "U1") (pin "33") (pinfunction "IOVDD_5_33") (pintype "power_in"))
      (node (ref "U1") (pin "42") (pinfunction "IOVDD_6_42") (pintype "power_in"))
      (node (ref "U1") (pin "44") (pinfunction "VREG_VIN_44") (pintype "passive"))
      (node (ref "U1") (pin "48") (pinfunction "USB_VDD_48") (pintype "power_in"))
      (node (ref "U1") (pin "49") (pinfunction "IOVDD_49") (pintype "power_in"))
      (node (ref "U2") (pin "8") (pinfunction "VCC_8") (pintype "power_in"))
      (node (ref "U3") (pin "5") (pinfunction "VREF_5") (pintype "power_in"))
      (node (ref "U5") (pin "1") (pinfunction "VDDI/O_1") (pintype "bidirectional"))
      (node (ref "U5") (pin "6") (pinfunction "VS_6") (pintype "bidirectional"))
      (node (ref "U7") (pin "15") (pinfunction "VCC_IO_15") (pintype "power_in"))
    )
    (net (code "3") (name "+5V") (class "Default")
      (node (ref "5V") (pin "P$1") (pinfunction "1_P$1") (pintype "bidirectional"))
      (node (ref "C14") (pin "1") (pinfunction "1_1") (pintype "passive"))
      (node (ref "C16") (pin "1") (pinfunction "1_1") (pintype "passive"))
      (node (ref "C21") (pin "1") (pinfunction "1_1") (pintype "passive"))
      (node (ref "C22") (pin "1") (pinfunction "1_1") (pintype "passive"))
      (node (ref "C27") (pin "1") (pinfunction "1_1") (pintype "passive"))
      (node (ref "C39") (pin "1") (pinfunction "1_1") (pintype "passive"))
      (node (ref "D1") (pin "1") (pinfunction "C_1") (pintype "passive"))
      (node (ref "IO3") (pin "P$1") (pinfunction "1_P$1") (pintype "bidirectional"))
      (node (ref "L1") (pin "2") (pinfunction "2_2") (pintype "bidirectional"))
      (node (ref "P2") (pin "1") (pinfunction "IN_1") (pintype "input"))
      (node (ref "P2") (pin "3") (pinfunction "EN_3") (pintype "input"))
      (node (ref "R7") (pin "2") (pinfunction "2_2") (pintype "passive"))
      (node (ref "U3") (pin "3") (pinfunction "VCC_3") (pintype "power_in"))
      (node (ref "U6") (pin "5") (pinfunction "VCC_5") (pintype "power_in"))
    )
    (net (code "4") (name "+24V") (class "Default")
      (node (ref "24V") (pin "P$1") (pinfunction "1_P$1") (pintype "bidirectional"))
      (node (ref "C18") (pin "1") (pinfunction "1_1") (pintype "passive"))
      (node (ref "C19") (pin "1") (pinfunction "1_1") (pintype "passive"))
      (node (ref "C29") (pin "1") (pinfunction "1_1") (pintype "passive"))
      (node (ref "C30") (pin "2") (pinfunction "2_2") (pintype "passive"))
      (node (ref "C31") (pin "2") (pinfunction "2_2") (pintype "passive"))
      (node (ref "C33") (pin "+") (pinfunction "+_+") (pintype "passive"))
      (node (ref "C38") (pin "1") (pinfunction "1_1") (pintype "passive"))
      (node (ref "C42") (pin "1") (pinfunction "1_1") (pintype "passive"))
      (node (ref "C43") (pin "1") (pinfunction "1_1") (pintype "passive"))
      (node (ref "C44") (pin "1") (pinfunction "1_1") (pintype "passive"))
      (node (ref "C45") (pin "1") (pinfunction "1_1") (pintype "passive"))
      (node (ref "J1") (pin "1") (pinfunction "1_1") (pintype "passive"))
      (node (ref "J3") (pin "2") (pinfunction "2_2") (pintype "passive"))
      (node (ref "P1") (pin "3") (pinfunction "VIN_3") (pintype "bidirectional"))
      (node (ref "R5") (pin "2") (pinfunction "2_2") (pintype "passive"))
      (node (ref "U7") (pin "22") (pinfunction "VS_2_22") (pintype "power_in"))
      (node (ref "U7") (pin "28") (pinfunction "VS_28") (pintype "power_in"))
      (node (ref "X5") (pin "2") (pinfunction "S_2") (pintype "passive"))
      (node (ref "X6") (pin "2") (pinfunction "S_2") (pintype "passive"))
      (node (ref "X7") (pin "2") (pinfunction "S_2") (pintype "passive"))
      (node (ref "X8") (pin "2") (pinfunction "S_2") (pintype "passive"))
    )
    (net (code "5") (name "A1") (class "Default")
      (node (ref "A1") (pin "P$1") (pinfunction "1_P$1") (pintype "bidirectional"))
      (node (ref "U7") (pin "24") (pinfunction "OA1_24") (pintype "output"))
      (node (ref "X4") (pin "2") (pinfunction "S_2") (pintype "passive"))
    )
    (net (code "6") (name "A2") (class "Default")
      (node (ref "A2") (pin "P$1") (pinfunction "1_P$1") (pintype "bidirectional"))
      (node (ref "U7") (pin "21") (pinfunction "OA2_21") (pintype "output"))
      (node (ref "X4") (pin "1") (pinfunction "S_1") (pintype "passive"))
    )
    (net (code "7") (name "ADC_AVDD") (class "Default")
      (node (ref "C13") (pin "1") (pinfunction "1_1") (pintype "passive"))
      (node (ref "R2") (pin "1") (pinfunction "1_1") (pintype "passive"))
      (node (ref "U1") (pin "43") (pinfunction "ADC_AVDD_43") (pintype "power_in"))
    )
    (net (code "8") (name "B1") (class "Default")
      (node (ref "B1") (pin "P$1") (pinfunction "1_P$1") (pintype "bidirectional"))
      (node (ref "U7") (pin "26") (pinfunction "OB1_26") (pintype "output"))
      (node (ref "X4") (pin "3") (pinfunction "S_3") (pintype "passive"))
    )
    (net (code "9") (name "B2") (class "Default")
      (node (ref "B2") (pin "P$1") (pinfunction "1_P$1") (pintype "bidirectional"))
      (node (ref "U7") (pin "1") (pinfunction "OB2_1") (pintype "output"))
      (node (ref "X4") (pin "4") (pinfunction "S_4") (pintype "passive"))
    )
    (net (code "10") (name "BRA") (class "Default")
      (node (ref "R27") (pin "2") (pinfunction "2_2") (pintype "passive"))
      (node (ref "U7") (pin "23") (pinfunction "BRA_23") (pintype "passive"))
    )
    (net (code "11") (name "BRB") (class "Default")
      (node (ref "R26") (pin "2") (pinfunction "2_2") (pintype "passive"))
      (node (ref "U7") (pin "27") (pinfunction "BRB_27") (pintype "passive"))
    )
    (net (code "12") (name "CAN_N") (class "Default")
      (node (ref "L2") (pin "3") (pinfunction "3_3") (pintype "passive"))
      (node (ref "SJ1") (pin "1") (pinfunction "1_1") (pintype "passive"))
      (node (ref "X2") (pin "2") (pinfunction "S_2") (pintype "passive"))
    )
    (net (code "13") (name "CAN_P") (class "Default")
      (node (ref "L2") (pin "4") (pinfunction "4_4") (pintype "passive"))
      (node (ref "R16") (pin "1") (pinfunction "1_1") (pintype "passive"))
      (node (ref "X2") (pin "1") (pinfunction "S_1") (pintype "passive"))
    )
    (net (code "14") (name "CAN_RX") (class "Default")
      (node (ref "U1") (pin "2") (pinfunction "GPIO0_2") (pintype "bidirectional"))
      (node (ref "U3") (pin "4") (pinfunction "RXD_4") (pintype "output"))
    )
    (net (code "15") (name "CAN_TX") (class "Default")
      (node (ref "U1") (pin "3") (pinfunction "GPIO1_3") (pintype "bidirectional"))
      (node (ref "U3") (pin "1") (pinfunction "TXD_1") (pintype "input"))
    )
    (net (code "16") (name "E0_DIAG") (class "Default")
      (node (ref "U1") (pin "39") (pinfunction "GPIO27/ADC1_39") (pintype "bidirectional"))
      (node (ref "U7") (pin "11") (pinfunction "DIAG_11") (pintype "output"))
    )
    (net (code "17") (name "E0_DIR") (class "Default")
      (node (ref "R25") (pin "1") (pinfunction "1_1") (pintype "passive"))
      (node (ref "U1") (pin "32") (pinfunction "GPIO21_32") (pintype "bidirectional"))
    )
    (net (code "18") (name "E0_EN") (class "Default")
      (node (ref "R23") (pin "2") (pinfunction "2_2") (pintype "passive"))
      (node (ref "U1") (pin "40") (pinfunction "GPIO28/ADC2_40") (pintype "bidirectional"))
    )
    (net (code "19") (name "E0_STEP") (class "Default")
      (node (ref "R24") (pin "1") (pinfunction "1_1") (pintype "passive"))
      (node (ref "U1") (pin "36") (pinfunction "GPIO24_36") (pintype "bidirectional"))
    )
    (net (code "20") (name "E0_UART") (class "Default")
      (node (ref "R22") (pin "2") (pinfunction "2_2") (pintype "passive"))
      (node (ref "U1") (pin "37") (pinfunction "GPIO25_37") (pintype "bidirectional"))
      (node (ref "U7") (pin "14") (pinfunction "PDN_UART_14") (pintype "bidirectional"))
    )
    (net (code "21") (name "ENDSTOP_X") (class "Default")
      (node (ref "R40") (pin "1") (pinfunction "1_1") (pintype "passive"))
      (node (ref "U1") (pin "9") (pinfunction "GPIO7_9") (pintype "bidirectional"))
    )
    (net (code "22") (name "FAN0") (class "Default")
      (node (ref "R44") (pin "2") (pinfunction "2_2") (pintype "passive"))
      (node (ref "R45") (pin "2") (pinfunction "2_2") (pintype "passive"))
      (node (ref "U1") (pin "11") (pinfunction "GPIO8_11") (pintype "bidirectional"))
    )
    (net (code "23") (name "FAN1") (class "Default")
      (node (ref "R46") (pin "2") (pinfunction "2_2") (pintype "passive"))
      (node (ref "R47") (pin "2") (pinfunction "2_2") (pintype "passive"))
      (node (ref "U1") (pin "12") (pinfunction "GPIO9_12") (pintype "bidirectional"))
    )
    (net (code "24") (name "FAN2") (class "Default")
      (node (ref "R48") (pin "2") (pinfunction "2_2") (pintype "passive"))
      (node (ref "R49") (pin "2") (pinfunction "2_2") (pintype "passive"))
      (node (ref "U1") (pin "13") (pinfunction "GPIO10_13") (pintype "bidirectional"))
    )
    (net (code "25") (name "GND") (class "Default")
      (node (ref "BOOT") (pin "1") (pinfunction "1_1") (pintype "bidirectional"))
      (node (ref "C1") (pin "2") (pinfunction "2_2") (pintype "passive"))
      (node (ref "C10") (pin "2") (pinfunction "2_2") (pintype "passive"))
      (node (ref "C11") (pin "2") (pinfunction "2_2") (pintype "passive"))
      (node (ref "C12") (pin "2") (pinfunction "2_2") (pintype "passive"))
      (node (ref "C13") (pin "2") (pinfunction "2_2") (pintype "passive"))
      (node (ref "C14") (pin "2") (pinfunction "2_2") (pintype "passive"))
      (node (ref "C15") (pin "2") (pinfunction "2_2") (pintype "passive"))
      (node (ref "C16") (pin "2") (pinfunction "2_2") (pintype "passive"))
      (node (ref "C17") (pin "2") (pinfunction "2_2") (pintype "passive"))
      (node (ref "C18") (pin "2") (pinfunction "2_2") (pintype "passive"))
      (node (ref "C19") (pin "2") (pinfunction "2_2") (pintype "passive"))
      (node (ref "C2") (pin "1") (pinfunction "1_1") (pintype "passive"))
      (node (ref "C21") (pin "2") (pinfunction "2_2") (pintype "passive"))
      (node (ref "C22") (pin "2") (pinfunction "2_2") (pintype "passive"))
      (node (ref "C24") (pin "2") (pinfunction "2_2") (pintype "passive"))
      (node (ref "C25") (pin "1") (pinfunction "1_1") (pintype "passive"))
      (node (ref "C26") (pin "2") (pinfunction "2_2") (pintype "passive"))
      (node (ref "C27") (pin "2") (pinfunction "2_2") (pintype "passive"))
      (node (ref "C3") (pin "2") (pinfunction "2_2") (pintype "passive"))
      (node (ref "C30") (pin "1") (pinfunction "1_1") (pintype "passive"))
      (node (ref "C31") (pin "1") (pinfunction "1_1") (pintype "passive"))
      (node (ref "C32") (pin "1") (pinfunction "1_1") (pintype "passive"))
      (node (ref "C33") (pin "-") (pinfunction "-_-") (pintype "passive"))
      (node (ref "C34") (pin "2") (pinfunction "2_2") (pintype "passive"))
      (node (ref "C38") (pin "2") (pinfunction "2_2") (pintype "passive"))
      (node (ref "C39") (pin "2") (pinfunction "2_2") (pintype "passive"))
      (node (ref "C4") (pin "2") (pinfunction "2_2") (pintype "passive"))
      (node (ref "C40") (pin "2") (pinfunction "2_2") (pintype "passive"))
      (node (ref "C42") (pin "2") (pinfunction "2_2") (pintype "passive"))
      (node (ref "C43") (pin "2") (pinfunction "2_2") (pintype "passive"))
      (node (ref "C44") (pin "2") (pinfunction "2_2") (pintype "passive"))
      (node (ref "C45") (pin "2") (pinfunction "2_2") (pintype "passive"))
      (node (ref "C5") (pin "2") (pinfunction "2_2") (pintype "passive"))
      (node (ref "C6") (pin "2") (pinfunction "2_2") (pintype "passive"))
      (node (ref "C7") (pin "2") (pinfunction "2_2") (pintype "passive"))
      (node (ref "C8") (pin "2") (pinfunction "2_2") (pintype "passive"))
      (node (ref "C9") (pin "2") (pinfunction "2_2") (pintype "passive"))
      (node (ref "D2") (pin "2") (pinfunction "GND_2") (pintype "power_in"))
      (node (ref "D3") (pin "C") (pinfunction "C_C") (pintype "passive"))
      (node (ref "D4") (pin "1") (pinfunction "1_1") (pintype "passive"))
      (node (ref "D6") (pin "1") (pinfunction "1_1") (pintype "passive"))
      (node (ref "D7") (pin "1") (pinfunction "1_1") (pintype "passive"))
      (node (ref "D8") (pin "1") (pinfunction "1_1") (pintype "passive"))
      (node (ref "D9") (pin "C") (pinfunction "C_C") (pintype "passive"))
      (node (ref "GND") (pin "P$1") (pinfunction "1_P$1") (pintype "bidirectional"))
      (node (ref "J1") (pin "2") (pinfunction "2_2") (pintype "passive"))
      (node (ref "J3") (pin "3") (pinfunction "3_3") (pintype "passive"))
      (node (ref "M1") (pin "P$1") (pinfunction "S_P$1") (pintype "passive"))
      (node (ref "M1") (pin "P$2") (pinfunction "S_P$2") (pintype "passive"))
      (node (ref "M1") (pin "P$3") (pinfunction "S_P$3") (pintype "passive"))
      (node (ref "M2") (pin "2") (pinfunction "S_2") (pintype "passive"))
      (node (ref "M3") (pin "2") (pinfunction "S_2") (pintype "passive"))
      (node (ref "M4") (pin "2") (pinfunction "S_2") (pintype "passive"))
      (node (ref "P1") (pin "1") (pinfunction "GND_1") (pintype "bidirectional"))
      (node (ref "P2") (pin "2") (pinfunction "GND_2") (pintype "input"))
      (node (ref "R22") (pin "1") (pinfunction "1_1") (pintype "passive"))
      (node (ref "R26") (pin "1") (pinfunction "1_1") (pintype "passive"))
      (node (ref "R27") (pin "1") (pinfunction "1_1") (pintype "passive"))
      (node (ref "R30") (pin "1") (pinfunction "1_1") (pintype "passive"))
      (node (ref "R37") (pin "1") (pinfunction "1_1") (pintype "passive"))
      (node (ref "R45") (pin "1") (pinfunction "1_1") (pintype "passive"))
      (node (ref "R47") (pin "1") (pinfunction "1_1") (pintype "passive"))
      (node (ref "R49") (pin "1") (pinfunction "1_1") (pintype "passive"))
      (node (ref "R6") (pin "1") (pinfunction "1_1") (pintype "passive"))
      (node (ref "R9") (pin "1") (pinfunction "1_1") (pintype "passive"))
      (node (ref "RST") (pin "1") (pinfunction "1_1") (pintype "bidirectional"))
      (node (ref "U1") (pin "19") (pinfunction "TESTEN_19") (pintype "passive"))
      (node (ref "U1") (pin "57") (pinfunction "GND_57") (pintype "passive"))
      (node (ref "U2") (pin "4") (pinfunction "GND_4") (pintype "passive"))
      (node (ref "U3") (pin "2") (pinfunction "GND_2") (pintype "power_in"))
      (node (ref "U3") (pin "8") (pinfunction "STBY_8") (pintype "input"))
      (node (ref "U5") (pin "2") (pinfunction "GND_2") (pintype "bidirectional"))
      (node (ref "U5") (pin "4") (pinfunction "GND1_4") (pintype "bidirectional"))
      (node (ref "U5") (pin "5") (pinfunction "GND2_5") (pintype "bidirectional"))
      (node (ref "U6") (pin "3") (pinfunction "GND_3") (pintype "power_in"))
      (node (ref "U7") (pin "13") (pinfunction "CLK_13") (pintype "input"))
      (node (ref "U7") (pin "18") (pinfunction "GND_18") (pintype "power_in"))
      (node (ref "U7") (pin "29") (pinfunction "EPAD_29") (pintype "passive"))
      (node (ref "U7") (pin "3") (pinfunction "GND_2_3") (pintype "power_in"))
      (node (ref "U7") (pin "7") (pinfunction "SPREAD_7") (pintype "input"))
      (node (ref "USB") (pin "1") (pinfunction "GND_1") (pintype "power_in"))
      (node (ref "USB") (pin "12") (pinfunction "GND2_12") (pintype "power_in"))
      (node (ref "USB") (pin "13") (pinfunction "SHLD_13") (pintype "passive"))
      (node (ref "USB") (pin "14") (pinfunction "SHLD_14") (pintype "passive"))
      (node (ref "USB") (pin "15") (pinfunction "SHLD_15") (pintype "passive"))
      (node (ref "USB") (pin "16") (pinfunction "SHLD_16") (pintype "passive"))
      (node (ref "USB") (pin "18") (pinfunction "SHLD_18") (pintype "passive"))
      (node (ref "USB") (pin "19") (pinfunction "SHLD_19") (pintype "passive"))
      (node (ref "USB") (pin "20") (pinfunction "SHLD_20") (pintype "passive"))
      (node (ref "USB") (pin "21") (pinfunction "SHLD_21") (pintype "passive"))
      (node (ref "USB") (pin "24") (pinfunction "SHLD_24") (pintype "passive"))
      (node (ref "USB") (pin "25") (pinfunction "SHLD_25") (pintype "passive"))
      (node (ref "USB") (pin "26") (pinfunction "SHLD_26") (pintype "passive"))
      (node (ref "USB") (pin "27") (pinfunction "SHLD_27") (pintype "passive"))
      (node (ref "USB") (pin "28") (pinfunction "SHLD_28") (pintype "passive"))
      (node (ref "USB") (pin "29") (pinfunction "SHLD_29") (pintype "passive"))
      (node (ref "USB") (pin "37") (pinfunction "SHLD_37") (pintype "passive"))
      (node (ref "USB") (pin "39") (pinfunction "SHLD_39") (pintype "passive"))
      (node (ref "USB") (pin "41") (pinfunction "SHLD_41") (pintype "passive"))
      (node (ref "USB") (pin "43") (pinfunction "SHLD_43") (pintype "passive"))
      (node (ref "X1") (pin "P$2") (pinfunction "GND_P$2") (pintype "bidirectional"))
      (node (ref "X1") (pin "P$4") (pinfunction "GND_P$4") (pintype "bidirectional"))
      (node (ref "X3") (pin "1") (pinfunction "S_1") (pintype "passive"))
    )
    (net (code "26") (name "HE0") (class "Default")
      (node (ref "HE0") (pin "P$1") (pinfunction "1_P$1") (pintype "bidirectional"))
      (node (ref "R37") (pin "2") (pinfunction "2_2") (pintype "passive"))
      (node (ref "U1") (pin "31") (pinfunction "GPIO20_31") (pintype "bidirectional"))
      (node (ref "U6") (pin "2") (pinfunction "A_2") (pintype "input"))
    )
    (net (code "27") (name "HE0_PWR") (class "Default")
      (node (ref "J3") (pin "1") (pinfunction "1_1") (pintype "passive"))
      (node (ref "M1") (pin "P$5") (pinfunction "D_P$5") (pintype "passive"))
      (node (ref "M1") (pin "P$6") (pinfunction "D_P$6") (pintype "passive"))
      (node (ref "M1") (pin "P$7") (pinfunction "D_P$7") (pintype "passive"))
      (node (ref "M1") (pin "P$8") (pinfunction "D_P$8") (pintype "passive"))
      (node (ref "M1") (pin "P$9") (pinfunction "D_P$9") (pintype "passive"))
    )
    (net (code "28") (name "I2C_SCL") (class "Default")
      (node (ref "U1") (pin "35") (pinfunction "GPIO23_35") (pintype "bidirectional"))
    )
    (net (code "29") (name "I2C_SDA") (class "Default")
      (node (ref "U1") (pin "34") (pinfunction "GPIO22_34") (pintype "bidirectional"))
    )
    (net (code "30") (name "Net-(BOOT-Pad2)") (class "Default")
      (node (ref "BOOT") (pin "2") (pinfunction "2_2") (pintype "bidirectional"))
      (node (ref "R12") (pin "2") (pinfunction "2_2") (pintype "passive"))
    )
    (net (code "31") (name "Net-(C23-Pad1)") (class "Default")
      (node (ref "C23") (pin "1") (pinfunction "1_1") (pintype "passive"))
      (node (ref "R7") (pin "1") (pinfunction "1_1") (pintype "passive"))
      (node (ref "R8") (pin "2") (pinfunction "2_2") (pintype "passive"))
    )
    (net (code "32") (name "Net-(D1-A)") (class "Default")
      (node (ref "D1") (pin "2") (pinfunction "A_2") (pintype "passive"))
      (node (ref "F1") (pin "1") (pinfunction "1_1") (pintype "passive"))
    )
    (net (code "33") (name "Net-(D2-I{slash}O1)") (class "Default")
      (node (ref "D2") (pin "1") (pinfunction "I/O1_2_1") (pintype "bidirectional"))
      (node (ref "D2") (pin "6") (pinfunction "I/O1_6") (pintype "bidirectional"))
      (node (ref "R10") (pin "1") (pinfunction "1_1") (pintype "passive"))
      (node (ref "USB") (pin "6") (pinfunction "AD+_6") (pintype "passive"))
      (node (ref "USB") (pin "7") (pinfunction "BD+_7") (pintype "passive"))
    )
    (net (code "34") (name "Net-(D2-I{slash}O2)") (class "Default")
      (node (ref "D2") (pin "3") (pinfunction "I/O2_2_3") (pintype "bidirectional"))
      (node (ref "D2") (pin "4") (pinfunction "I/O2_4") (pintype "bidirectional"))
      (node (ref "R11") (pin "1") (pinfunction "1_1") (pintype "passive"))
      (node (ref "USB") (pin "5") (pinfunction "BD-_5") (pintype "passive"))
      (node (ref "USB") (pin "8") (pinfunction "AD-_8") (pintype "passive"))
    )
    (net (code "35") (name "Net-(D2-VBUS)") (class "Default")
      (node (ref "D2") (pin "5") (pinfunction "VBUS_5") (pintype "power_in"))
      (node (ref "F1") (pin "2") (pinfunction "2_2") (pintype "passive"))
      (node (ref "SJ3") (pin "1") (pinfunction "1_1") (pintype "passive"))
    )
    (net (code "36") (name "Net-(D3-PadA)") (class "Default")
      (node (ref "D3") (pin "A") (pinfunction "A_A") (pintype "passive"))
      (node (ref "R15") (pin "1") (pinfunction "1_1") (pintype "passive"))
    )
    (net (code "37") (name "Net-(D4-Pad3)") (class "Default")
      (node (ref "D4") (pin "3") (pinfunction "3_3") (pintype "passive"))
      (node (ref "R35") (pin "2") (pinfunction "2_2") (pintype "passive"))
      (node (ref "R36") (pin "1") (pinfunction "1_1") (pintype "passive"))
    )
    (net (code "38") (name "Net-(D9-PadA)") (class "Default")
      (node (ref "D9") (pin "A") (pinfunction "A_A") (pintype "passive"))
      (node (ref "R28") (pin "1") (pinfunction "1_1") (pintype "passive"))
    )
    (net (code "39") (name "Net-(J3-Pad4)") (class "Default")
      (node (ref "J3") (pin "4") (pinfunction "4_4") (pintype "passive"))
      (node (ref "R33") (pin "1") (pinfunction "1_1") (pintype "passive"))
      (node (ref "R34") (pin "1") (pinfunction "1_1") (pintype "passive"))
      (node (ref "R35") (pin "1") (pinfunction "1_1") (pintype "passive"))
    )
    (net (code "40") (name "Net-(M1-G)") (class "Default")
      (node (ref "M1") (pin "P$4") (pinfunction "G_P$4") (pintype "passive"))
      (node (ref "R31") (pin "1") (pinfunction "1_1") (pintype "passive"))
    )
    (net (code "41") (name "Net-(M2-D)") (class "Default")
      (node (ref "M2") (pin "3") (pinfunction "D_3") (pintype "passive"))
      (node (ref "X5") (pin "1") (pinfunction "S_1") (pintype "passive"))
    )
    (net (code "42") (name "Net-(M2-G)") (class "Default")
      (node (ref "D6") (pin "3") (pinfunction "3_3") (pintype "passive"))
      (node (ref "M2") (pin "1") (pinfunction "G_1") (pintype "passive"))
      (node (ref "R44") (pin "1") (pinfunction "1_1") (pintype "passive"))
    )
    (net (code "43") (name "Net-(M3-D)") (class "Default")
      (node (ref "M3") (pin "3") (pinfunction "D_3") (pintype "passive"))
      (node (ref "X6") (pin "1") (pinfunction "S_1") (pintype "passive"))
    )
    (net (code "44") (name "Net-(M3-G)") (class "Default")
      (node (ref "D7") (pin "3") (pinfunction "3_3") (pintype "passive"))
      (node (ref "M3") (pin "1") (pinfunction "G_1") (pintype "passive"))
      (node (ref "R46") (pin "1") (pinfunction "1_1") (pintype "passive"))
    )
    (net (code "45") (name "Net-(M4-D)") (class "Default")
      (node (ref "M4") (pin "3") (pinfunction "D_3") (pintype "passive"))
      (node (ref "X7") (pin "1") (pinfunction "S_1") (pintype "passive"))
      (node (ref "X8") (pin "1") (pinfunction "S_1") (pintype "passive"))
    )
    (net (code "46") (name "Net-(M4-G)") (class "Default")
      (node (ref "D8") (pin "3") (pinfunction "3_3") (pintype "passive"))
      (node (ref "M4") (pin "1") (pinfunction "G_1") (pintype "passive"))
      (node (ref "R48") (pin "1") (pinfunction "1_1") (pintype "passive"))
    )
    (net (code "47") (name "Net-(P1-BOOT)") (class "Default")
      (node (ref "C20") (pin "1") (pinfunction "1_1") (pintype "passive"))
      (node (ref "P1") (pin "6") (pinfunction "BOOT_6") (pintype "bidirectional"))
    )
    (net (code "48") (name "Net-(P1-EN)") (class "Default")
      (node (ref "P1") (pin "5") (pinfunction "EN_5") (pintype "bidirectional"))
      (node (ref "R5") (pin "1") (pinfunction "1_1") (pintype "passive"))
      (node (ref "R6") (pin "2") (pinfunction "2_2") (pintype "passive"))
    )
    (net (code "49") (name "Net-(P1-FB)") (class "Default")
      (node (ref "C23") (pin "2") (pinfunction "2_2") (pintype "passive"))
      (node (ref "P1") (pin "4") (pinfunction "FB_4") (pintype "bidirectional"))
      (node (ref "R8") (pin "1") (pinfunction "1_1") (pintype "passive"))
      (node (ref "R9") (pin "2") (pinfunction "2_2") (pintype "passive"))
    )
    (net (code "50") (name "Net-(P1-SW)") (class "Default")
      (node (ref "C20") (pin "2") (pinfunction "2_2") (pintype "passive"))
      (node (ref "L1") (pin "1") (pinfunction "1_1") (pintype "bidirectional"))
      (node (ref "P1") (pin "2") (pinfunction "SW_2") (pintype "bidirectional"))
    )
    (net (code "51") (name "Net-(R1-Pad1)") (class "Default")
      (node (ref "R1") (pin "1") (pinfunction "1_1") (pintype "passive"))
      (node (ref "R2") (pin "2") (pinfunction "2_2") (pintype "passive"))
    )
    (net (code "52") (name "Net-(R16-Pad2)") (class "Default")
      (node (ref "R16") (pin "2") (pinfunction "2_2") (pintype "passive"))
      (node (ref "SJ1") (pin "2") (pinfunction "2_2") (pintype "passive"))
    )
    (net (code "53") (name "Net-(R34-Pad2)") (class "Default")
      (node (ref "R34") (pin "2") (pinfunction "2_2") (pintype "passive"))
      (node (ref "SJ2") (pin "1") (pinfunction "1_1") (pintype "passive"))
    )
    (net (code "54") (name "Net-(U1-GPIO2)") (class "Default")
      (node (ref "R28") (pin "2") (pinfunction "2_2") (pintype "passive"))
      (node (ref "U1") (pin "4") (pinfunction "GPIO2_4") (pintype "bidirectional"))
    )
    (net (code "55") (name "Net-(U3-CANH)") (class "Default")
      (node (ref "L2") (pin "1") (pinfunction "1_1") (pintype "passive"))
      (node (ref "U3") (pin "7") (pinfunction "CANH_7") (pintype "output"))
    )
    (net (code "56") (name "Net-(U3-CANL)") (class "Default")
      (node (ref "L2") (pin "2") (pinfunction "2_2") (pintype "passive"))
      (node (ref "U3") (pin "6") (pinfunction "CANL_6") (pintype "output"))
    )
    (net (code "57") (name "Net-(U6-Y)") (class "Default")
      (node (ref "R30") (pin "2") (pinfunction "2_2") (pintype "passive"))
      (node (ref "R31") (pin "2") (pinfunction "2_2") (pintype "passive"))
      (node (ref "U6") (pin "4") (pinfunction "Y_4") (pintype "output"))
    )
    (net (code "58") (name "Net-(U7-5VOUT)") (class "Default")
      (node (ref "C32") (pin "2") (pinfunction "2_2") (pintype "passive"))
      (node (ref "U7") (pin "8") (pinfunction "5VOUT_8") (pintype "output"))
    )
    (net (code "59") (name "Net-(U7-CPI)") (class "Default")
      (node (ref "C28") (pin "1") (pinfunction "1_1") (pintype "passive"))
      (node (ref "U7") (pin "5") (pinfunction "CPI_5") (pintype "input"))
    )
    (net (code "60") (name "Net-(U7-CPO)") (class "Default")
      (node (ref "C28") (pin "2") (pinfunction "2_2") (pintype "passive"))
      (node (ref "U7") (pin "4") (pinfunction "CPO_4") (pintype "output"))
    )
    (net (code "61") (name "Net-(U7-DIR)") (class "Default")
      (node (ref "R25") (pin "2") (pinfunction "2_2") (pintype "passive"))
      (node (ref "U7") (pin "19") (pinfunction "DIR_19") (pintype "input"))
    )
    (net (code "62") (name "Net-(U7-ENN)") (class "Default")
      (node (ref "R21") (pin "2") (pinfunction "2_2") (pintype "passive"))
      (node (ref "R23") (pin "1") (pinfunction "1_1") (pintype "passive"))
      (node (ref "U7") (pin "2") (pinfunction "ENN_2") (pintype "input"))
    )
    (net (code "63") (name "Net-(U7-STEP)") (class "Default")
      (node (ref "R24") (pin "2") (pinfunction "2_2") (pintype "passive"))
      (node (ref "U7") (pin "16") (pinfunction "STEP_16") (pintype "input"))
    )
    (net (code "64") (name "Net-(U7-VCP)") (class "Default")
      (node (ref "C29") (pin "2") (pinfunction "2_2") (pintype "passive"))
      (node (ref "U7") (pin "6") (pinfunction "VCP_6") (pintype "power_in"))
    )
    (net (code "65") (name "Net-(X1-P2)") (class "Default")
      (node (ref "C2") (pin "2") (pinfunction "2_2") (pintype "passive"))
      (node (ref "R3") (pin "1") (pinfunction "1_1") (pintype "passive"))
      (node (ref "X1") (pin "P$3") (pinfunction "P2_P$3") (pintype "bidirectional"))
    )
    (net (code "66") (name "Net-(X3B-S)") (class "Default")
      (node (ref "R40") (pin "2") (pinfunction "2_2") (pintype "passive"))
      (node (ref "R41") (pin "2") (pinfunction "2_2") (pintype "passive"))
      (node (ref "X3") (pin "2") (pinfunction "S_2") (pintype "passive"))
    )
    (net (code "67") (name "OSC_IN") (class "Default")
      (node (ref "C1") (pin "1") (pinfunction "1_1") (pintype "passive"))
      (node (ref "R4") (pin "2") (pinfunction "2_2") (pintype "passive"))
      (node (ref "U1") (pin "20") (pinfunction "XIN_20") (pintype "passive"))
      (node (ref "X1") (pin "P$1") (pinfunction "P1_P$1") (pintype "bidirectional"))
    )
    (net (code "68") (name "OSC_OUT") (class "Default")
      (node (ref "R3") (pin "2") (pinfunction "2_2") (pintype "passive"))
      (node (ref "R4") (pin "1") (pinfunction "1_1") (pintype "passive"))
      (node (ref "U1") (pin "21") (pinfunction "XOUT_21") (pintype "output"))
    )
    (net (code "69") (name "QSPI_SCK") (class "Default")
      (node (ref "U1") (pin "52") (pinfunction "QSPI_SCLK_52") (pintype "passive"))
      (node (ref "U2") (pin "6") (pinfunction "CLK_6") (pintype "passive"))
    )
    (net (code "70") (name "QSPI_SD0") (class "Default")
      (node (ref "U1") (pin "53") (pinfunction "QSPI_SD0_53") (pintype "bidirectional"))
      (node (ref "U2") (pin "5") (pinfunction "DI_(IO0)_5") (pintype "passive"))
    )
    (net (code "71") (name "QSPI_SD1") (class "Default")
      (node (ref "U1") (pin "55") (pinfunction "QSPI_SD1_55") (pintype "bidirectional"))
      (node (ref "U2") (pin "2") (pinfunction "DO_(IO1)_2") (pintype "passive"))
    )
    (net (code "72") (name "QSPI_SD2") (class "Default")
      (node (ref "U1") (pin "54") (pinfunction "QSPI_SD2_54") (pintype "bidirectional"))
      (node (ref "U2") (pin "3") (pinfunction "/WP_(IO2)_3") (pintype "passive"))
    )
    (net (code "73") (name "QSPI_SD3") (class "Default")
      (node (ref "U1") (pin "51") (pinfunction "QSPI_SD3_51") (pintype "bidirectional"))
      (node (ref "U2") (pin "7") (pinfunction "/RESET_(IO3)_7") (pintype "passive"))
    )
    (net (code "74") (name "QSPI_SS") (class "Default")
      (node (ref "R12") (pin "1") (pinfunction "1_1") (pintype "passive"))
      (node (ref "R13") (pin "1") (pinfunction "1_1") (pintype "passive"))
      (node (ref "U1") (pin "56") (pinfunction "QSPI_SS_N_56") (pintype "passive"))
      (node (ref "U2") (pin "1") (pinfunction "/CS_1") (pintype "passive"))
    )
    (net (code "75") (name "RESET") (class "Default")
      (node (ref "C25") (pin "2") (pinfunction "2_2") (pintype "passive"))
      (node (ref "R14") (pin "1") (pinfunction "1_1") (pintype "passive"))
      (node (ref "RST") (pin "2") (pinfunction "2_2") (pintype "bidirectional"))
      (node (ref "U1") (pin "26") (pinfunction "RUN_26") (pintype "passive"))
    )
    (net (code "76") (name "SPI0_CS") (class "Default")
      (node (ref "U1") (pin "28") (pinfunction "GPIO17_28") (pintype "bidirectional"))
    )
    (net (code "77") (name "SPI0_MISO") (class "Default")
      (node (ref "U1") (pin "27") (pinfunction "GPIO16_27") (pintype "bidirectional"))
    )
    (net (code "78") (name "SPI0_MOSI") (class "Default")
      (node (ref "U1") (pin "30") (pinfunction "GPIO19_30") (pintype "bidirectional"))
    )
    (net (code "79") (name "SPI0_SCK") (class "Default")
      (node (ref "U1") (pin "29") (pinfunction "GPIO18_29") (pintype "bidirectional"))
    )
    (net (code "80") (name "SPI1_CS") (class "Default")
      (node (ref "R19") (pin "1") (pinfunction "1_1") (pintype "passive"))
      (node (ref "U1") (pin "16") (pinfunction "GPIO13_16") (pintype "bidirectional"))
      (node (ref "U5") (pin "7") (pinfunction "~{CS}_7") (pintype "bidirectional"))
    )
    (net (code "81") (name "SPI1_MISO") (class "Default")
      (node (ref "R18") (pin "1") (pinfunction "1_1") (pintype "passive"))
      (node (ref "U1") (pin "15") (pinfunction "GPIO12_15") (pintype "bidirectional"))
      (node (ref "U5") (pin "12") (pinfunction "SDO/ALT_ADDRESS_12") (pintype "bidirectional"))
    )
    (net (code "82") (name "SPI1_MOSI") (class "Default")
      (node (ref "R17") (pin "1") (pinfunction "1_1") (pintype "passive"))
      (node (ref "U1") (pin "18") (pinfunction "GPIO15_18") (pintype "bidirectional"))
      (node (ref "U5") (pin "13") (pinfunction "SDA/SDI/SDIO_13") (pintype "bidirectional"))
    )
    (net (code "83") (name "SPI1_SCK") (class "Default")
      (node (ref "R20") (pin "1") (pinfunction "1_1") (pintype "passive"))
      (node (ref "U1") (pin "17") (pinfunction "GPIO14_17") (pintype "bidirectional"))
      (node (ref "U5") (pin "14") (pinfunction "SCL/SCLK_14") (pintype "bidirectional"))
    )
    (net (code "84") (name "SWCLK") (class "Default")
      (node (ref "U1") (pin "24") (pinfunction "SWCLK_24") (pintype "passive"))
    )
    (net (code "85") (name "SWDIO") (class "Default")
      (node (ref "U1") (pin "25") (pinfunction "SWDIO_25") (pintype "passive"))
    )
    (net (code "86") (name "TH0") (class "Default")
      (node (ref "C40") (pin "1") (pinfunction "1_1") (pintype "passive"))
      (node (ref "R36") (pin "2") (pinfunction "2_2") (pintype "passive"))
      (node (ref "TH0") (pin "P$1") (pinfunction "1_P$1") (pintype "bidirectional"))
      (node (ref "U1") (pin "38") (pinfunction "GPIO26/ADC0_38") (pintype "bidirectional"))
    )
    (net (code "87") (name "USB_N") (class "Default")
      (node (ref "IO1") (pin "P$1") (pinfunction "1_P$1") (pintype "bidirectional"))
      (node (ref "R11") (pin "2") (pinfunction "2_2") (pintype "passive"))
      (node (ref "U1") (pin "46") (pinfunction "USB_DM_46") (pintype "passive"))
    )
    (net (code "88") (name "USB_P") (class "Default")
      (node (ref "IO2") (pin "P$1") (pinfunction "1_P$1") (pintype "bidirectional"))
      (node (ref "R10") (pin "2") (pinfunction "2_2") (pintype "passive"))
      (node (ref "U1") (pin "47") (pinfunction "USB_DP_47") (pintype "passive"))
    )
    (net (code "89") (name "VBUS") (class "Default")
      (node (ref "SJ3") (pin "2") (pinfunction "2_2") (pintype "passive"))
      (node (ref "USB") (pin "11") (pinfunction "VBUS2_11") (pintype "power_in"))
      (node (ref "USB") (pin "2") (pinfunction "VBUS_2") (pintype "power_in"))
    )
    (net (code "90") (name "unconnected-(P2-NC-Pad4)") (class "Default")
      (node (ref "P2") (pin "4") (pinfunction "NC_4") (pintype "no_connect"))
    )
    (net (code "91") (name "unconnected-(U1-GPIO3-Pad5)") (class "Default")
      (node (ref "U1") (pin "5") (pinfunction "GPIO3_5") (pintype "bidirectional"))
    )
    (net (code "92") (name "unconnected-(U1-GPIO4-Pad6)") (class "Default")
      (node (ref "U1") (pin "6") (pinfunction "GPIO4_6") (pintype "bidirectional"))
    )
    (net (code "93") (name "unconnected-(U1-GPIO5-Pad7)") (class "Default")
      (node (ref "U1") (pin "7") (pinfunction "GPIO5_7") (pintype "bidirectional"))
    )
    (net (code "94") (name "unconnected-(U1-GPIO6-Pad8)") (class "Default")
      (node (ref "U1") (pin "8") (pinfunction "GPIO6_8") (pintype "bidirectional"))
    )
    (net (code "95") (name "unconnected-(U1-GPIO11-Pad14)") (class "Default")
      (node (ref "U1") (pin "14") (pinfunction "GPIO11_14") (pintype "bidirectional"))
    )
    (net (code "96") (name "unconnected-(U1-GPIO29{slash}ADC3-Pad41)") (class "Default")
      (node (ref "U1") (pin "41") (pinfunction "GPIO29/ADC3_41") (pintype "bidirectional"))
    )
    (net (code "97") (name "unconnected-(U5-INT1-Pad8)") (class "Default")
      (node (ref "U5") (pin "8") (pinfunction "INT1_8") (pintype "bidirectional"))
    )
    (net (code "98") (name "unconnected-(U5-INT2-Pad9)") (class "Default")
      (node (ref "U5") (pin "9") (pinfunction "INT2_9") (pintype "bidirectional"))
    )
    (net (code "99") (name "unconnected-(U5-NC-Pad10)") (class "Default")
      (node (ref "U5") (pin "10") (pinfunction "NC_10") (pintype "bidirectional"))
    )
    (net (code "100") (name "unconnected-(U5-RESERVED-Pad3)") (class "Default")
      (node (ref "U5") (pin "3") (pinfunction "RESERVED_3") (pintype "bidirectional"))
    )
    (net (code "101") (name "unconnected-(U5-RESERVED1-Pad11)") (class "Default")
      (node (ref "U5") (pin "11") (pinfunction "RESERVED1_11") (pintype "bidirectional"))
    )
    (net (code "102") (name "unconnected-(U6-NC-Pad1)") (class "Default")
      (node (ref "U6") (pin "1") (pinfunction "NC_1") (pintype "passive"))
    )
    (net (code "103") (name "unconnected-(U7-INDEX-Pad12)") (class "Default")
      (node (ref "U7") (pin "12") (pinfunction "INDEX_12") (pintype "output"))
    )
    (net (code "104") (name "unconnected-(U7-MS1_AD0-Pad9)") (class "Default")
      (node (ref "U7") (pin "9") (pinfunction "MS1_AD0_9") (pintype "input"))
    )
    (net (code "105") (name "unconnected-(U7-MS2_AD1-Pad10)") (class "Default")
      (node (ref "U7") (pin "10") (pinfunction "MS2_AD1_10") (pintype "input"))
    )
    (net (code "106") (name "unconnected-(U7-NC-Pad25)") (class "Default")
      (node (ref "U7") (pin "25") (pinfunction "NC_25") (pintype "no_connect"))
    )
    (net (code "107") (name "unconnected-(U7-STDBY-Pad20)") (class "Default")
      (node (ref "U7") (pin "20") (pinfunction "STDBY_20") (pintype "input"))
    )
    (net (code "108") (name "unconnected-(U7-VREF-Pad17)") (class "Default")
      (node (ref "U7") (pin "17") (pinfunction "VREF_17") (pintype "input"))
    )
    (net (code "109") (name "unconnected-(USB-CC1-Pad3)") (class "Default")
      (node (ref "USB") (pin "3") (pinfunction "CC1_3") (pintype "passive"))
    )
    (net (code "110") (name "unconnected-(USB-CC2-Pad9)") (class "Default")
      (node (ref "USB") (pin "9") (pinfunction "CC2_9") (pintype "passive"))
    )
    (net (code "111") (name "unconnected-(USB-SBU1-Pad10)") (class "Default")
      (node (ref "USB") (pin "10") (pinfunction "SBU1_10") (pintype "passive"))
    )
    (net (code "112") (name "unconnected-(USB-SBU2-Pad4)") (class "Default")
      (node (ref "USB") (pin "4") (pinfunction "SBU2_4") (pintype "passive"))
    )
  )
)
